# Debug_board.net
KiCad netlist of a schematic drawn in EAGLE
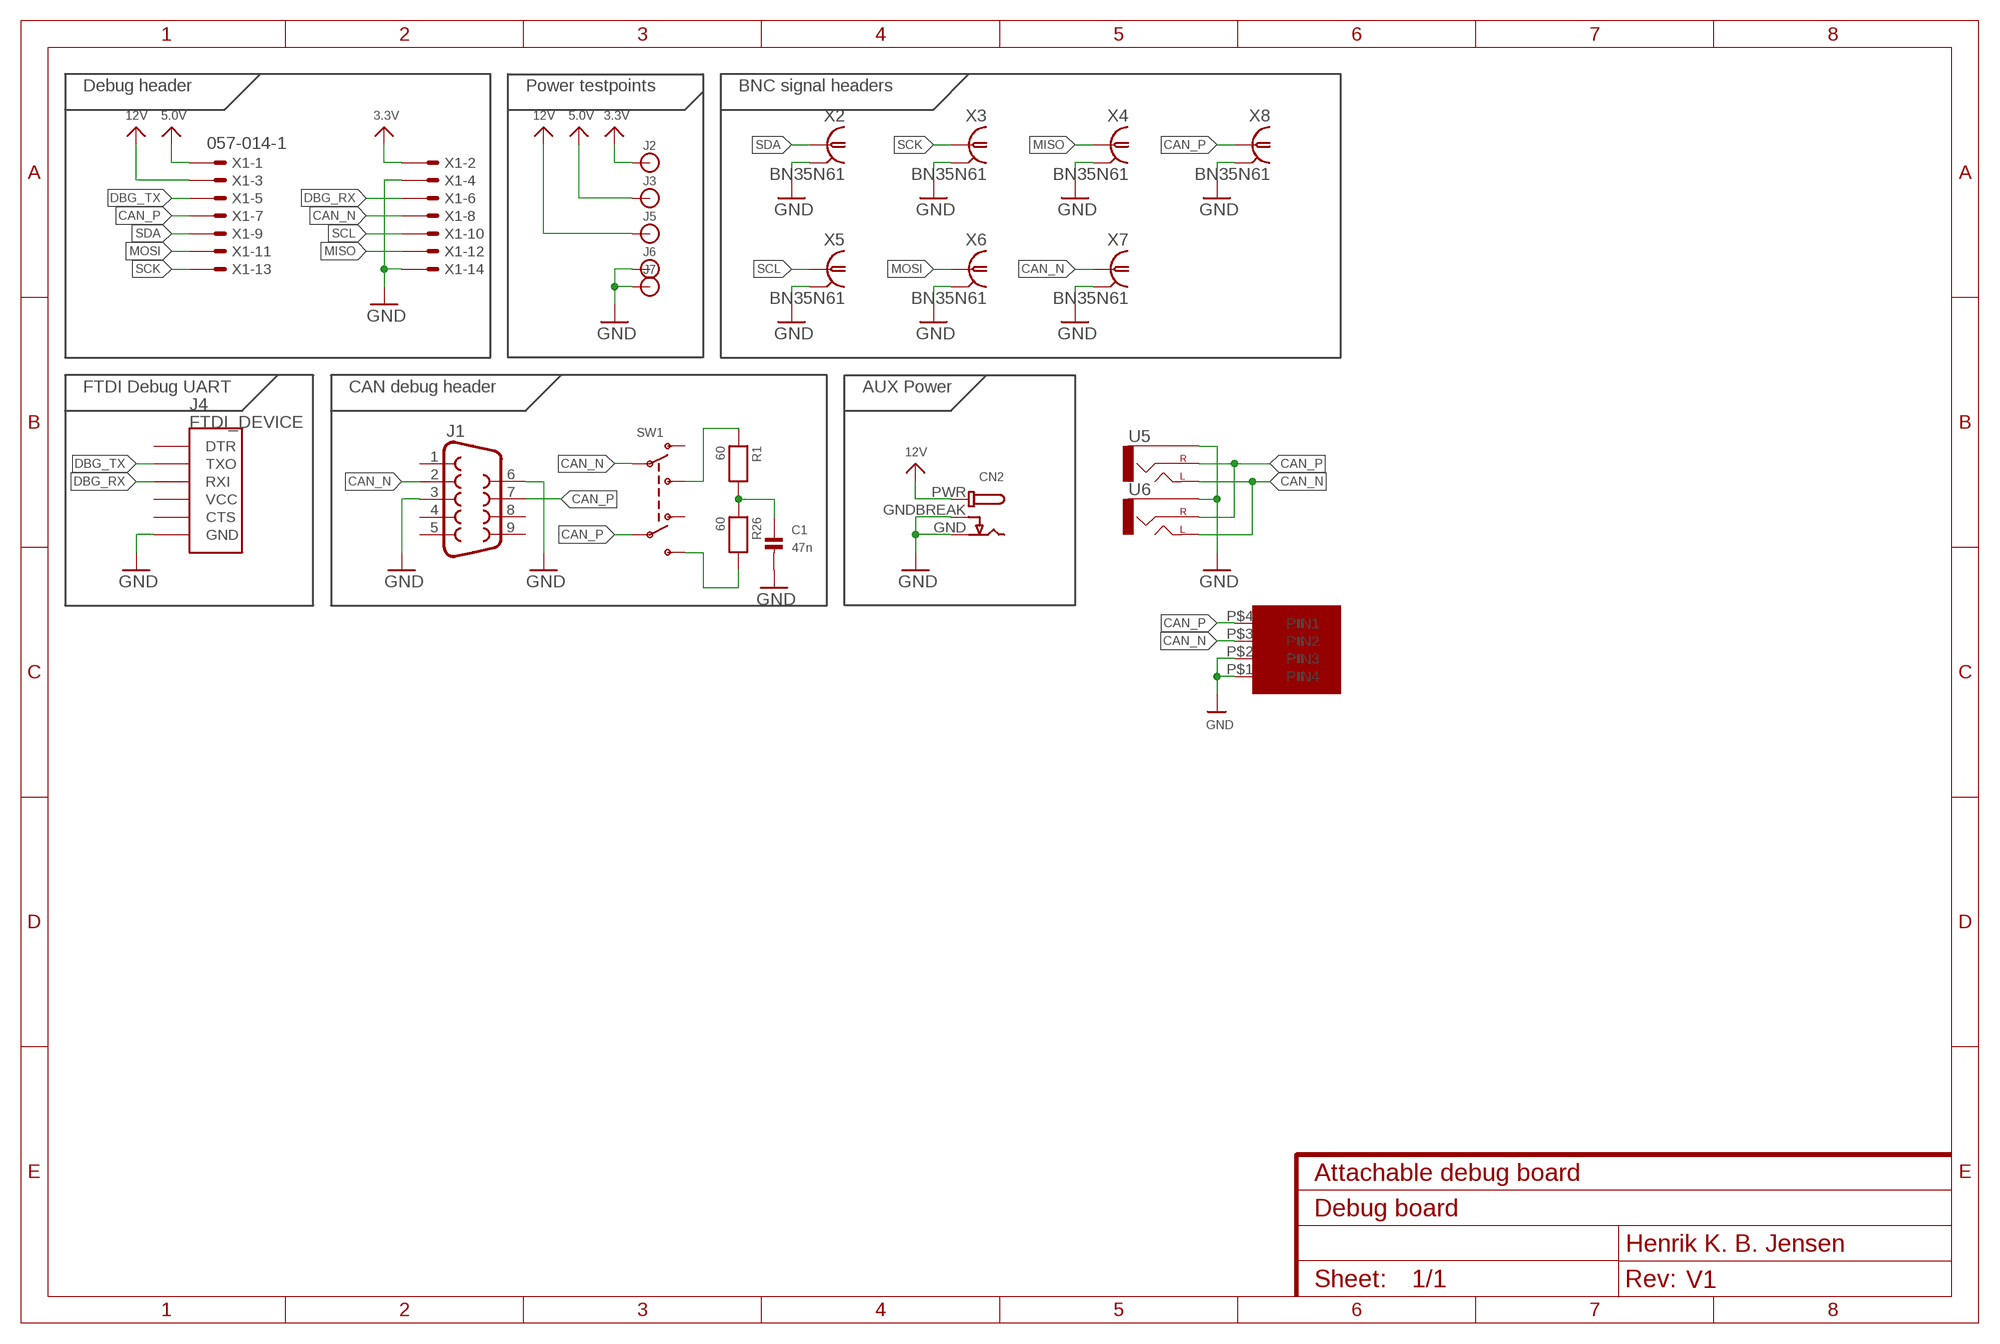
[diagram p0: schematic, sheet 1]

(export (version "E")
  (design (tool "Eeschema 10.0.6"))
  (components
    (comp (ref "C1")
      (value "47n")
      (footprint "eagle-import:_0603")
      (libsource (lib "eagle-import") (part "CAP_CERAMIC_0603"))
    )
    (comp (ref "CN2")
      (value "DCBARRELPTH")
      (footprint "eagle-import:DCJACK_2MM_PTH")
      (libsource (lib "eagle-import") (part "DCBARRELPTH"))
    )
    (comp (ref "J1")
      (value "DB9FEMALE")
      (footprint "eagle-import:DB9")
      (libsource (lib "eagle-import") (part "DB9FEMALE"))
    )
    (comp (ref "J2")
      (value "BANANA_CONN")
      (footprint "eagle-import:BANANA_CONN")
      (libsource (lib "eagle-import") (part "BANANA_CONN"))
    )
    (comp (ref "J3")
      (value "BANANA_CONN")
      (footprint "eagle-import:BANANA_CONN")
      (libsource (lib "eagle-import") (part "BANANA_CONN"))
    )
    (comp (ref "J4")
      (value "FTDI_DEVICE")
      (footprint "eagle-import:FTDI_DEVICE_SIDE")
      (libsource (lib "eagle-import") (part "FTDI_DEVICE"))
    )
    (comp (ref "J5")
      (value "BANANA_CONN")
      (footprint "eagle-import:BANANA_CONN")
      (libsource (lib "eagle-import") (part "BANANA_CONN"))
    )
    (comp (ref "J6")
      (value "BANANA_CONN")
      (footprint "eagle-import:BANANA_CONN")
      (libsource (lib "eagle-import") (part "BANANA_CONN"))
    )
    (comp (ref "J7")
      (value "BANANA_CONN")
      (footprint "eagle-import:BANANA_CONN")
      (libsource (lib "eagle-import") (part "BANANA_CONN"))
    )
    (comp (ref "R1")
      (value "60")
      (footprint "eagle-import:_0603")
      (libsource (lib "eagle-import") (part "RESISTOR_0603"))
    )
    (comp (ref "R26")
      (value "60")
      (footprint "eagle-import:_0603")
      (libsource (lib "eagle-import") (part "RESISTOR_0603"))
    )
    (comp (ref "SW1")
      (value "SWITCH_DPDT")
      (footprint "eagle-import:DPDT_SMT_JS202011SCQN")
      (libsource (lib "eagle-import") (part "SWITCH_DPDT"))
    )
    (comp (ref "U$21")
      (value "MICROFIT4")
      (footprint "eagle-import:43045-0400")
      (libsource (lib "eagle-import") (part "MICROFIT4"))
    )
    (comp (ref "U5")
      (value "AUDIO-JACKPTH")
      (footprint "eagle-import:AUDIO-JACK")
      (libsource (lib "eagle-import") (part "AUDIO-JACKPTH"))
    )
    (comp (ref "U6")
      (value "AUDIO-JACKPTH")
      (footprint "eagle-import:AUDIO-JACK")
      (libsource (lib "eagle-import") (part "AUDIO-JACKPTH"))
    )
    (comp (ref "X1")
      (value "057-014-1")
      (footprint "eagle-import:057-014-1")
      (libsource (lib "eagle-import") (part "057-014-1"))
    )
    (comp (ref "X2")
      (value "BN35N61")
      (footprint "eagle-import:B35N61")
      (libsource (lib "eagle-import") (part "BN35N61"))
    )
    (comp (ref "X3")
      (value "BN35N61")
      (footprint "eagle-import:B35N61")
      (libsource (lib "eagle-import") (part "BN35N61"))
    )
    (comp (ref "X4")
      (value "BN35N61")
      (footprint "eagle-import:B35N61")
      (libsource (lib "eagle-import") (part "BN35N61"))
    )
    (comp (ref "X5")
      (value "BN35N61")
      (footprint "eagle-import:B35N61")
      (libsource (lib "eagle-import") (part "BN35N61"))
    )
    (comp (ref "X6")
      (value "BN35N61")
      (footprint "eagle-import:B35N61")
      (libsource (lib "eagle-import") (part "BN35N61"))
    )
    (comp (ref "X7")
      (value "BN35N61")
      (footprint "eagle-import:B35N61")
      (libsource (lib "eagle-import") (part "BN35N61"))
    )
    (comp (ref "X8")
      (value "BN35N61")
      (footprint "eagle-import:B35N61")
      (libsource (lib "eagle-import") (part "BN35N61"))
    )
  )
  (nets
    (net (code "1") (name "3.3V") (class "Default")
      (node (ref "J2") (pin "P$1") (pinfunction "1_P$1") (pintype "passive"))
      (node (ref "X1") (pin "2") (pinfunction "S_2") (pintype "passive"))
    )
    (net (code "2") (name "5.0V") (class "Default")
      (node (ref "J3") (pin "P$1") (pinfunction "1_P$1") (pintype "passive"))
      (node (ref "X1") (pin "1") (pinfunction "S_1") (pintype "passive"))
    )
    (net (code "3") (name "12V") (class "Default")
      (node (ref "CN2") (pin "PWR") (pinfunction "PWR_PWR") (pintype "power_in"))
      (node (ref "J5") (pin "P$1") (pinfunction "1_P$1") (pintype "passive"))
      (node (ref "X1") (pin "3") (pinfunction "S_3") (pintype "passive"))
    )
    (net (code "4") (name "CAN_N") (class "Default")
      (node (ref "J1") (pin "2") (pinfunction "2_2") (pintype "passive"))
      (node (ref "SW1") (pin "P$2") (pinfunction "P1_P$2") (pintype "passive"))
      (node (ref "U$21") (pin "P$3") (pinfunction "PIN2_P$3") (pintype "bidirectional"))
      (node (ref "U5") (pin "TIP") (pinfunction "LEFT_TIP") (pintype "bidirectional"))
      (node (ref "U6") (pin "TIP") (pinfunction "LEFT_TIP") (pintype "bidirectional"))
      (node (ref "X1") (pin "8") (pinfunction "S_8") (pintype "passive"))
      (node (ref "X7") (pin "1") (pinfunction "1_1") (pintype "passive"))
    )
    (net (code "5") (name "CAN_P") (class "Default")
      (node (ref "J1") (pin "7") (pinfunction "7_7") (pintype "passive"))
      (node (ref "SW1") (pin "P$5") (pinfunction "P2_P$5") (pintype "passive"))
      (node (ref "U$21") (pin "P$4") (pinfunction "PIN1_P$4") (pintype "bidirectional"))
      (node (ref "U5") (pin "RING") (pinfunction "RIGHT_RING") (pintype "bidirectional"))
      (node (ref "U6") (pin "RING") (pinfunction "RIGHT_RING") (pintype "bidirectional"))
      (node (ref "X1") (pin "7") (pinfunction "S_7") (pintype "passive"))
      (node (ref "X8") (pin "1") (pinfunction "1_1") (pintype "passive"))
    )
    (net (code "6") (name "DBG_RX") (class "Default")
      (node (ref "J4") (pin "P$3") (pinfunction "RXI_P$3") (pintype "bidirectional"))
      (node (ref "X1") (pin "6") (pinfunction "S_6") (pintype "passive"))
    )
    (net (code "7") (name "DBG_TX") (class "Default")
      (node (ref "J4") (pin "P$2") (pinfunction "TXO_P$2") (pintype "bidirectional"))
      (node (ref "X1") (pin "5") (pinfunction "S_5") (pintype "passive"))
    )
    (net (code "8") (name "GND") (class "Default")
      (node (ref "C1") (pin "2") (pinfunction "P$2_2") (pintype "passive"))
      (node (ref "CN2") (pin "GND") (pinfunction "GND_GND") (pintype "power_in"))
      (node (ref "CN2") (pin "GNDBREAK") (pinfunction "GNDBREAK_GNDBREAK") (pintype "power_in"))
      (node (ref "J1") (pin "3") (pinfunction "3_3") (pintype "passive"))
      (node (ref "J1") (pin "6") (pinfunction "6_6") (pintype "passive"))
      (node (ref "J4") (pin "P$6") (pinfunction "GND_P$6") (pintype "bidirectional"))
      (node (ref "J6") (pin "P$1") (pinfunction "1_P$1") (pintype "passive"))
      (node (ref "J7") (pin "P$1") (pinfunction "1_P$1") (pintype "passive"))
      (node (ref "U$21") (pin "P$1") (pinfunction "PIN4_P$1") (pintype "bidirectional"))
      (node (ref "U$21") (pin "P$2") (pinfunction "PIN3_P$2") (pintype "bidirectional"))
      (node (ref "U5") (pin "SLEEVE") (pinfunction "SLEEVE_SLEEVE") (pintype "bidirectional"))
      (node (ref "U6") (pin "SLEEVE") (pinfunction "SLEEVE_SLEEVE") (pintype "bidirectional"))
      (node (ref "X1") (pin "14") (pinfunction "S_14") (pintype "passive"))
      (node (ref "X1") (pin "4") (pinfunction "S_4") (pintype "passive"))
      (node (ref "X2") (pin "2") (pinfunction "GND_2") (pintype "power_in"))
      (node (ref "X3") (pin "2") (pinfunction "GND_2") (pintype "power_in"))
      (node (ref "X4") (pin "2") (pinfunction "GND_2") (pintype "power_in"))
      (node (ref "X5") (pin "2") (pinfunction "GND_2") (pintype "power_in"))
      (node (ref "X6") (pin "2") (pinfunction "GND_2") (pintype "power_in"))
      (node (ref "X7") (pin "2") (pinfunction "GND_2") (pintype "power_in"))
      (node (ref "X8") (pin "2") (pinfunction "GND_2") (pintype "power_in"))
    )
    (net (code "9") (name "MISO") (class "Default")
      (node (ref "X1") (pin "12") (pinfunction "S_12") (pintype "passive"))
      (node (ref "X4") (pin "1") (pinfunction "1_1") (pintype "passive"))
    )
    (net (code "10") (name "MOSI") (class "Default")
      (node (ref "X1") (pin "11") (pinfunction "S_11") (pintype "passive"))
      (node (ref "X6") (pin "1") (pinfunction "1_1") (pintype "passive"))
    )
    (net (code "11") (name "Net-(C1-P$1)") (class "Default")
      (node (ref "C1") (pin "1") (pinfunction "P$1_1") (pintype "passive"))
      (node (ref "R1") (pin "2") (pinfunction "2_2") (pintype "passive"))
      (node (ref "R26") (pin "1") (pinfunction "1_1") (pintype "passive"))
    )
    (net (code "12") (name "Net-(SW1-S1)") (class "Default")
      (node (ref "R1") (pin "1") (pinfunction "1_1") (pintype "passive"))
      (node (ref "SW1") (pin "P$3") (pinfunction "S1_P$3") (pintype "passive"))
    )
    (net (code "13") (name "Net-(SW1-S2)") (class "Default")
      (node (ref "R26") (pin "2") (pinfunction "2_2") (pintype "passive"))
      (node (ref "SW1") (pin "P$4") (pinfunction "S2_P$4") (pintype "passive"))
    )
    (net (code "14") (name "SCK") (class "Default")
      (node (ref "X1") (pin "13") (pinfunction "S_13") (pintype "passive"))
      (node (ref "X3") (pin "1") (pinfunction "1_1") (pintype "passive"))
    )
    (net (code "15") (name "SCL") (class "Default")
      (node (ref "X1") (pin "10") (pinfunction "S_10") (pintype "passive"))
      (node (ref "X5") (pin "1") (pinfunction "1_1") (pintype "passive"))
    )
    (net (code "16") (name "SDA") (class "Default")
      (node (ref "X1") (pin "9") (pinfunction "S_9") (pintype "passive"))
      (node (ref "X2") (pin "1") (pinfunction "1_1") (pintype "passive"))
    )
    (net (code "17") (name "unconnected-(J1-Pad1)") (class "Default")
      (node (ref "J1") (pin "1") (pinfunction "1_1") (pintype "passive"))
    )
    (net (code "18") (name "unconnected-(J1-Pad4)") (class "Default")
      (node (ref "J1") (pin "4") (pinfunction "4_4") (pintype "passive"))
    )
    (net (code "19") (name "unconnected-(J1-Pad5)") (class "Default")
      (node (ref "J1") (pin "5") (pinfunction "5_5") (pintype "passive"))
    )
    (net (code "20") (name "unconnected-(J1-Pad8)") (class "Default")
      (node (ref "J1") (pin "8") (pinfunction "8_8") (pintype "passive"))
    )
    (net (code "21") (name "unconnected-(J1-Pad9)") (class "Default")
      (node (ref "J1") (pin "9") (pinfunction "9_9") (pintype "passive"))
    )
    (net (code "22") (name "unconnected-(J4-CTS-PadP$5)") (class "Default")
      (node (ref "J4") (pin "P$5") (pinfunction "CTS_P$5") (pintype "bidirectional"))
    )
    (net (code "23") (name "unconnected-(J4-DTR-PadP$1)") (class "Default")
      (node (ref "J4") (pin "P$1") (pinfunction "DTR_P$1") (pintype "bidirectional"))
    )
    (net (code "24") (name "unconnected-(J4-VCC-PadP$4)") (class "Default")
      (node (ref "J4") (pin "P$4") (pinfunction "VCC_P$4") (pintype "bidirectional"))
    )
    (net (code "25") (name "unconnected-(SW1-O1-PadP$1)") (class "Default")
      (node (ref "SW1") (pin "P$1") (pinfunction "O1_P$1") (pintype "passive"))
    )
    (net (code "26") (name "unconnected-(SW1-O2-PadP$6)") (class "Default")
      (node (ref "SW1") (pin "P$6") (pinfunction "O2_P$6") (pintype "passive"))
    )
  )
)
